# output_schematic_Z.net
KiCad netlist of a schematic drawn in EasyEDA
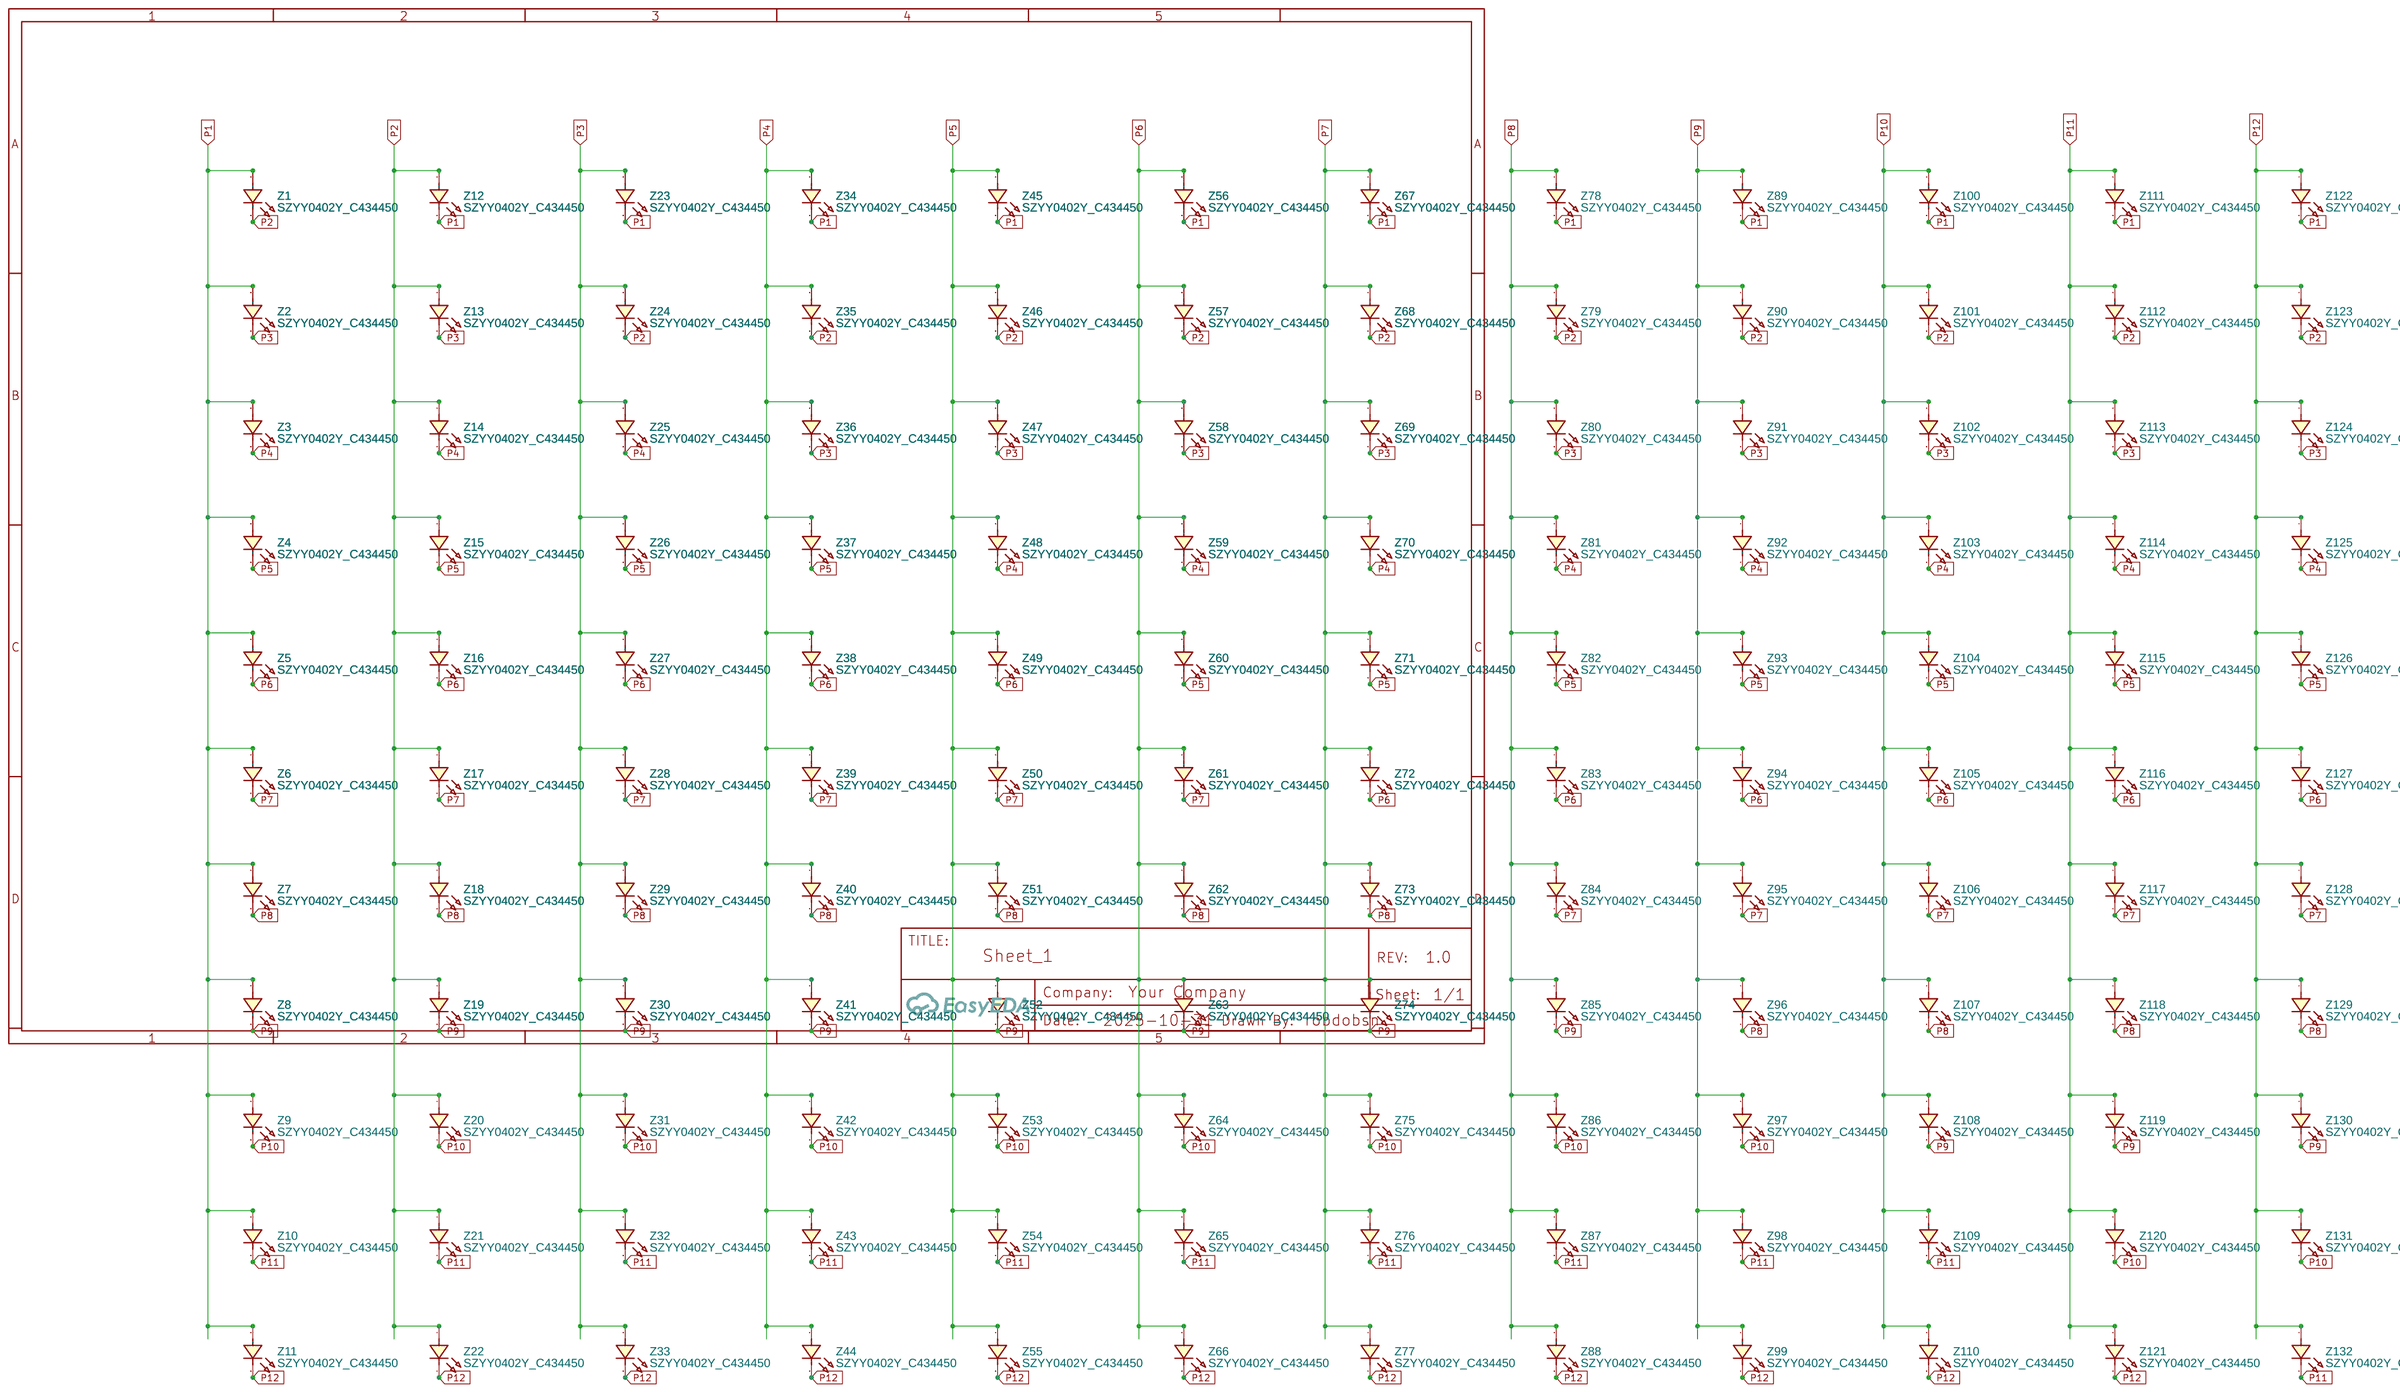
[diagram p0: schematic sheet]

(export (version "E")
  (design (tool "Eeschema 10.0.6"))
  (components
    (comp (ref "Z1")
      (value "SZYY0402Y_C434450")
      (fields (field (name "Manufacturer Part") "SZYY0402Y") (field (name "Manufacturer") "yongyu(永裕光电)"))
      (libsource (lib "") (part "SZYY0402Y_C434450"))
    )
    (comp (ref "Z2")
      (value "SZYY0402Y_C434450")
      (fields (field (name "Manufacturer Part") "SZYY0402Y") (field (name "Manufacturer") "yongyu(永裕光电)"))
      (libsource (lib "") (part "SZYY0402Y_C434450"))
    )
    (comp (ref "Z3")
      (value "SZYY0402Y_C434450")
      (fields (field (name "Manufacturer Part") "SZYY0402Y") (field (name "Manufacturer") "yongyu(永裕光电)"))
      (libsource (lib "") (part "SZYY0402Y_C434450"))
    )
    (comp (ref "Z4")
      (value "SZYY0402Y_C434450")
      (fields (field (name "Manufacturer Part") "SZYY0402Y") (field (name "Manufacturer") "yongyu(永裕光电)"))
      (libsource (lib "") (part "SZYY0402Y_C434450"))
    )
    (comp (ref "Z5")
      (value "SZYY0402Y_C434450")
      (fields (field (name "Manufacturer Part") "SZYY0402Y") (field (name "Manufacturer") "yongyu(永裕光电)"))
      (libsource (lib "") (part "SZYY0402Y_C434450"))
    )
    (comp (ref "Z6")
      (value "SZYY0402Y_C434450")
      (fields (field (name "Manufacturer Part") "SZYY0402Y") (field (name "Manufacturer") "yongyu(永裕光电)"))
      (libsource (lib "") (part "SZYY0402Y_C434450"))
    )
    (comp (ref "Z7")
      (value "SZYY0402Y_C434450")
      (fields (field (name "Manufacturer Part") "SZYY0402Y") (field (name "Manufacturer") "yongyu(永裕光电)"))
      (libsource (lib "") (part "SZYY0402Y_C434450"))
    )
    (comp (ref "Z8")
      (value "SZYY0402Y_C434450")
      (fields (field (name "Manufacturer Part") "SZYY0402Y") (field (name "Manufacturer") "yongyu(永裕光电)"))
      (libsource (lib "") (part "SZYY0402Y_C434450"))
    )
    (comp (ref "Z9")
      (value "SZYY0402Y_C434450")
      (fields (field (name "Manufacturer Part") "SZYY0402Y") (field (name "Manufacturer") "yongyu(永裕光电)"))
      (libsource (lib "") (part "SZYY0402Y_C434450"))
    )
    (comp (ref "Z10")
      (value "SZYY0402Y_C434450")
      (fields (field (name "Manufacturer Part") "SZYY0402Y") (field (name "Manufacturer") "yongyu(永裕光电)"))
      (libsource (lib "") (part "SZYY0402Y_C434450"))
    )
    (comp (ref "Z11")
      (value "SZYY0402Y_C434450")
      (fields (field (name "Manufacturer Part") "SZYY0402Y") (field (name "Manufacturer") "yongyu(永裕光电)"))
      (libsource (lib "") (part "SZYY0402Y_C434450"))
    )
    (comp (ref "Z12")
      (value "SZYY0402Y_C434450")
      (fields (field (name "Manufacturer Part") "SZYY0402Y") (field (name "Manufacturer") "yongyu(永裕光电)"))
      (libsource (lib "") (part "SZYY0402Y_C434450"))
    )
    (comp (ref "Z13")
      (value "SZYY0402Y_C434450")
      (fields (field (name "Manufacturer Part") "SZYY0402Y") (field (name "Manufacturer") "yongyu(永裕光电)"))
      (libsource (lib "") (part "SZYY0402Y_C434450"))
    )
    (comp (ref "Z14")
      (value "SZYY0402Y_C434450")
      (fields (field (name "Manufacturer Part") "SZYY0402Y") (field (name "Manufacturer") "yongyu(永裕光电)"))
      (libsource (lib "") (part "SZYY0402Y_C434450"))
    )
    (comp (ref "Z15")
      (value "SZYY0402Y_C434450")
      (fields (field (name "Manufacturer Part") "SZYY0402Y") (field (name "Manufacturer") "yongyu(永裕光电)"))
      (libsource (lib "") (part "SZYY0402Y_C434450"))
    )
    (comp (ref "Z16")
      (value "SZYY0402Y_C434450")
      (fields (field (name "Manufacturer Part") "SZYY0402Y") (field (name "Manufacturer") "yongyu(永裕光电)"))
      (libsource (lib "") (part "SZYY0402Y_C434450"))
    )
    (comp (ref "Z17")
      (value "SZYY0402Y_C434450")
      (fields (field (name "Manufacturer Part") "SZYY0402Y") (field (name "Manufacturer") "yongyu(永裕光电)"))
      (libsource (lib "") (part "SZYY0402Y_C434450"))
    )
    (comp (ref "Z18")
      (value "SZYY0402Y_C434450")
      (fields (field (name "Manufacturer Part") "SZYY0402Y") (field (name "Manufacturer") "yongyu(永裕光电)"))
      (libsource (lib "") (part "SZYY0402Y_C434450"))
    )
    (comp (ref "Z19")
      (value "SZYY0402Y_C434450")
      (fields (field (name "Manufacturer Part") "SZYY0402Y") (field (name "Manufacturer") "yongyu(永裕光电)"))
      (libsource (lib "") (part "SZYY0402Y_C434450"))
    )
    (comp (ref "Z20")
      (value "SZYY0402Y_C434450")
      (fields (field (name "Manufacturer Part") "SZYY0402Y") (field (name "Manufacturer") "yongyu(永裕光电)"))
      (libsource (lib "") (part "SZYY0402Y_C434450"))
    )
    (comp (ref "Z21")
      (value "SZYY0402Y_C434450")
      (fields (field (name "Manufacturer Part") "SZYY0402Y") (field (name "Manufacturer") "yongyu(永裕光电)"))
      (libsource (lib "") (part "SZYY0402Y_C434450"))
    )
    (comp (ref "Z22")
      (value "SZYY0402Y_C434450")
      (fields (field (name "Manufacturer Part") "SZYY0402Y") (field (name "Manufacturer") "yongyu(永裕光电)"))
      (libsource (lib "") (part "SZYY0402Y_C434450"))
    )
    (comp (ref "Z23")
      (value "SZYY0402Y_C434450")
      (fields (field (name "Manufacturer Part") "SZYY0402Y") (field (name "Manufacturer") "yongyu(永裕光电)"))
      (libsource (lib "") (part "SZYY0402Y_C434450"))
    )
    (comp (ref "Z24")
      (value "SZYY0402Y_C434450")
      (fields (field (name "Manufacturer Part") "SZYY0402Y") (field (name "Manufacturer") "yongyu(永裕光电)"))
      (libsource (lib "") (part "SZYY0402Y_C434450"))
    )
    (comp (ref "Z25")
      (value "SZYY0402Y_C434450")
      (fields (field (name "Manufacturer Part") "SZYY0402Y") (field (name "Manufacturer") "yongyu(永裕光电)"))
      (libsource (lib "") (part "SZYY0402Y_C434450"))
    )
    (comp (ref "Z26")
      (value "SZYY0402Y_C434450")
      (fields (field (name "Manufacturer Part") "SZYY0402Y") (field (name "Manufacturer") "yongyu(永裕光电)"))
      (libsource (lib "") (part "SZYY0402Y_C434450"))
    )
    (comp (ref "Z27")
      (value "SZYY0402Y_C434450")
      (fields (field (name "Manufacturer Part") "SZYY0402Y") (field (name "Manufacturer") "yongyu(永裕光电)"))
      (libsource (lib "") (part "SZYY0402Y_C434450"))
    )
    (comp (ref "Z28")
      (value "SZYY0402Y_C434450")
      (fields (field (name "Manufacturer Part") "SZYY0402Y") (field (name "Manufacturer") "yongyu(永裕光电)"))
      (libsource (lib "") (part "SZYY0402Y_C434450"))
    )
    (comp (ref "Z29")
      (value "SZYY0402Y_C434450")
      (fields (field (name "Manufacturer Part") "SZYY0402Y") (field (name "Manufacturer") "yongyu(永裕光电)"))
      (libsource (lib "") (part "SZYY0402Y_C434450"))
    )
    (comp (ref "Z30")
      (value "SZYY0402Y_C434450")
      (fields (field (name "Manufacturer Part") "SZYY0402Y") (field (name "Manufacturer") "yongyu(永裕光电)"))
      (libsource (lib "") (part "SZYY0402Y_C434450"))
    )
    (comp (ref "Z31")
      (value "SZYY0402Y_C434450")
      (fields (field (name "Manufacturer Part") "SZYY0402Y") (field (name "Manufacturer") "yongyu(永裕光电)"))
      (libsource (lib "") (part "SZYY0402Y_C434450"))
    )
    (comp (ref "Z32")
      (value "SZYY0402Y_C434450")
      (fields (field (name "Manufacturer Part") "SZYY0402Y") (field (name "Manufacturer") "yongyu(永裕光电)"))
      (libsource (lib "") (part "SZYY0402Y_C434450"))
    )
    (comp (ref "Z33")
      (value "SZYY0402Y_C434450")
      (fields (field (name "Manufacturer Part") "SZYY0402Y") (field (name "Manufacturer") "yongyu(永裕光电)"))
      (libsource (lib "") (part "SZYY0402Y_C434450"))
    )
    (comp (ref "Z34")
      (value "SZYY0402Y_C434450")
      (fields (field (name "Manufacturer Part") "SZYY0402Y") (field (name "Manufacturer") "yongyu(永裕光电)"))
      (libsource (lib "") (part "SZYY0402Y_C434450"))
    )
    (comp (ref "Z35")
      (value "SZYY0402Y_C434450")
      (fields (field (name "Manufacturer Part") "SZYY0402Y") (field (name "Manufacturer") "yongyu(永裕光电)"))
      (libsource (lib "") (part "SZYY0402Y_C434450"))
    )
    (comp (ref "Z36")
      (value "SZYY0402Y_C434450")
      (fields (field (name "Manufacturer Part") "SZYY0402Y") (field (name "Manufacturer") "yongyu(永裕光电)"))
      (libsource (lib "") (part "SZYY0402Y_C434450"))
    )
    (comp (ref "Z37")
      (value "SZYY0402Y_C434450")
      (fields (field (name "Manufacturer Part") "SZYY0402Y") (field (name "Manufacturer") "yongyu(永裕光电)"))
      (libsource (lib "") (part "SZYY0402Y_C434450"))
    )
    (comp (ref "Z38")
      (value "SZYY0402Y_C434450")
      (fields (field (name "Manufacturer Part") "SZYY0402Y") (field (name "Manufacturer") "yongyu(永裕光电)"))
      (libsource (lib "") (part "SZYY0402Y_C434450"))
    )
    (comp (ref "Z39")
      (value "SZYY0402Y_C434450")
      (fields (field (name "Manufacturer Part") "SZYY0402Y") (field (name "Manufacturer") "yongyu(永裕光电)"))
      (libsource (lib "") (part "SZYY0402Y_C434450"))
    )
    (comp (ref "Z40")
      (value "SZYY0402Y_C434450")
      (fields (field (name "Manufacturer Part") "SZYY0402Y") (field (name "Manufacturer") "yongyu(永裕光电)"))
      (libsource (lib "") (part "SZYY0402Y_C434450"))
    )
    (comp (ref "Z41")
      (value "SZYY0402Y_C434450")
      (fields (field (name "Manufacturer Part") "SZYY0402Y") (field (name "Manufacturer") "yongyu(永裕光电)"))
      (libsource (lib "") (part "SZYY0402Y_C434450"))
    )
    (comp (ref "Z42")
      (value "SZYY0402Y_C434450")
      (fields (field (name "Manufacturer Part") "SZYY0402Y") (field (name "Manufacturer") "yongyu(永裕光电)"))
      (libsource (lib "") (part "SZYY0402Y_C434450"))
    )
    (comp (ref "Z43")
      (value "SZYY0402Y_C434450")
      (fields (field (name "Manufacturer Part") "SZYY0402Y") (field (name "Manufacturer") "yongyu(永裕光电)"))
      (libsource (lib "") (part "SZYY0402Y_C434450"))
    )
    (comp (ref "Z44")
      (value "SZYY0402Y_C434450")
      (fields (field (name "Manufacturer Part") "SZYY0402Y") (field (name "Manufacturer") "yongyu(永裕光电)"))
      (libsource (lib "") (part "SZYY0402Y_C434450"))
    )
    (comp (ref "Z45")
      (value "SZYY0402Y_C434450")
      (fields (field (name "Manufacturer Part") "SZYY0402Y") (field (name "Manufacturer") "yongyu(永裕光电)"))
      (libsource (lib "") (part "SZYY0402Y_C434450"))
    )
    (comp (ref "Z46")
      (value "SZYY0402Y_C434450")
      (fields (field (name "Manufacturer Part") "SZYY0402Y") (field (name "Manufacturer") "yongyu(永裕光电)"))
      (libsource (lib "") (part "SZYY0402Y_C434450"))
    )
    (comp (ref "Z47")
      (value "SZYY0402Y_C434450")
      (fields (field (name "Manufacturer Part") "SZYY0402Y") (field (name "Manufacturer") "yongyu(永裕光电)"))
      (libsource (lib "") (part "SZYY0402Y_C434450"))
    )
    (comp (ref "Z48")
      (value "SZYY0402Y_C434450")
      (fields (field (name "Manufacturer Part") "SZYY0402Y") (field (name "Manufacturer") "yongyu(永裕光电)"))
      (libsource (lib "") (part "SZYY0402Y_C434450"))
    )
    (comp (ref "Z49")
      (value "SZYY0402Y_C434450")
      (fields (field (name "Manufacturer Part") "SZYY0402Y") (field (name "Manufacturer") "yongyu(永裕光电)"))
      (libsource (lib "") (part "SZYY0402Y_C434450"))
    )
    (comp (ref "Z50")
      (value "SZYY0402Y_C434450")
      (fields (field (name "Manufacturer Part") "SZYY0402Y") (field (name "Manufacturer") "yongyu(永裕光电)"))
      (libsource (lib "") (part "SZYY0402Y_C434450"))
    )
    (comp (ref "Z51")
      (value "SZYY0402Y_C434450")
      (fields (field (name "Manufacturer Part") "SZYY0402Y") (field (name "Manufacturer") "yongyu(永裕光电)"))
      (libsource (lib "") (part "SZYY0402Y_C434450"))
    )
    (comp (ref "Z52")
      (value "SZYY0402Y_C434450")
      (fields (field (name "Manufacturer Part") "SZYY0402Y") (field (name "Manufacturer") "yongyu(永裕光电)"))
      (libsource (lib "") (part "SZYY0402Y_C434450"))
    )
    (comp (ref "Z53")
      (value "SZYY0402Y_C434450")
      (fields (field (name "Manufacturer Part") "SZYY0402Y") (field (name "Manufacturer") "yongyu(永裕光电)"))
      (libsource (lib "") (part "SZYY0402Y_C434450"))
    )
    (comp (ref "Z54")
      (value "SZYY0402Y_C434450")
      (fields (field (name "Manufacturer Part") "SZYY0402Y") (field (name "Manufacturer") "yongyu(永裕光电)"))
      (libsource (lib "") (part "SZYY0402Y_C434450"))
    )
    (comp (ref "Z55")
      (value "SZYY0402Y_C434450")
      (fields (field (name "Manufacturer Part") "SZYY0402Y") (field (name "Manufacturer") "yongyu(永裕光电)"))
      (libsource (lib "") (part "SZYY0402Y_C434450"))
    )
    (comp (ref "Z56")
      (value "SZYY0402Y_C434450")
      (fields (field (name "Manufacturer Part") "SZYY0402Y") (field (name "Manufacturer") "yongyu(永裕光电)"))
      (libsource (lib "") (part "SZYY0402Y_C434450"))
    )
    (comp (ref "Z57")
      (value "SZYY0402Y_C434450")
      (fields (field (name "Manufacturer Part") "SZYY0402Y") (field (name "Manufacturer") "yongyu(永裕光电)"))
      (libsource (lib "") (part "SZYY0402Y_C434450"))
    )
    (comp (ref "Z58")
      (value "SZYY0402Y_C434450")
      (fields (field (name "Manufacturer Part") "SZYY0402Y") (field (name "Manufacturer") "yongyu(永裕光电)"))
      (libsource (lib "") (part "SZYY0402Y_C434450"))
    )
    (comp (ref "Z59")
      (value "SZYY0402Y_C434450")
      (fields (field (name "Manufacturer Part") "SZYY0402Y") (field (name "Manufacturer") "yongyu(永裕光电)"))
      (libsource (lib "") (part "SZYY0402Y_C434450"))
    )
    (comp (ref "Z60")
      (value "SZYY0402Y_C434450")
      (fields (field (name "Manufacturer Part") "SZYY0402Y") (field (name "Manufacturer") "yongyu(永裕光电)"))
      (libsource (lib "") (part "SZYY0402Y_C434450"))
    )
    (comp (ref "Z61")
      (value "SZYY0402Y_C434450")
      (fields (field (name "Manufacturer Part") "SZYY0402Y") (field (name "Manufacturer") "yongyu(永裕光电)"))
      (libsource (lib "") (part "SZYY0402Y_C434450"))
    )
    (comp (ref "Z62")
      (value "SZYY0402Y_C434450")
      (fields (field (name "Manufacturer Part") "SZYY0402Y") (field (name "Manufacturer") "yongyu(永裕光电)"))
      (libsource (lib "") (part "SZYY0402Y_C434450"))
    )
    (comp (ref "Z63")
      (value "SZYY0402Y_C434450")
      (fields (field (name "Manufacturer Part") "SZYY0402Y") (field (name "Manufacturer") "yongyu(永裕光电)"))
      (libsource (lib "") (part "SZYY0402Y_C434450"))
    )
    (comp (ref "Z64")
      (value "SZYY0402Y_C434450")
      (fields (field (name "Manufacturer Part") "SZYY0402Y") (field (name "Manufacturer") "yongyu(永裕光电)"))
      (libsource (lib "") (part "SZYY0402Y_C434450"))
    )
    (comp (ref "Z65")
      (value "SZYY0402Y_C434450")
      (fields (field (name "Manufacturer Part") "SZYY0402Y") (field (name "Manufacturer") "yongyu(永裕光电)"))
      (libsource (lib "") (part "SZYY0402Y_C434450"))
    )
    (comp (ref "Z66")
      (value "SZYY0402Y_C434450")
      (fields (field (name "Manufacturer Part") "SZYY0402Y") (field (name "Manufacturer") "yongyu(永裕光电)"))
      (libsource (lib "") (part "SZYY0402Y_C434450"))
    )
    (comp (ref "Z67")
      (value "SZYY0402Y_C434450")
      (fields (field (name "Manufacturer Part") "SZYY0402Y") (field (name "Manufacturer") "yongyu(永裕光电)"))
      (libsource (lib "") (part "SZYY0402Y_C434450"))
    )
    (comp (ref "Z68")
      (value "SZYY0402Y_C434450")
      (fields (field (name "Manufacturer Part") "SZYY0402Y") (field (name "Manufacturer") "yongyu(永裕光电)"))
      (libsource (lib "") (part "SZYY0402Y_C434450"))
    )
    (comp (ref "Z69")
      (value "SZYY0402Y_C434450")
      (fields (field (name "Manufacturer Part") "SZYY0402Y") (field (name "Manufacturer") "yongyu(永裕光电)"))
      (libsource (lib "") (part "SZYY0402Y_C434450"))
    )
    (comp (ref "Z70")
      (value "SZYY0402Y_C434450")
      (fields (field (name "Manufacturer Part") "SZYY0402Y") (field (name "Manufacturer") "yongyu(永裕光电)"))
      (libsource (lib "") (part "SZYY0402Y_C434450"))
    )
    (comp (ref "Z71")
      (value "SZYY0402Y_C434450")
      (fields (field (name "Manufacturer Part") "SZYY0402Y") (field (name "Manufacturer") "yongyu(永裕光电)"))
      (libsource (lib "") (part "SZYY0402Y_C434450"))
    )
    (comp (ref "Z72")
      (value "SZYY0402Y_C434450")
      (fields (field (name "Manufacturer Part") "SZYY0402Y") (field (name "Manufacturer") "yongyu(永裕光电)"))
      (libsource (lib "") (part "SZYY0402Y_C434450"))
    )
    (comp (ref "Z73")
      (value "SZYY0402Y_C434450")
      (fields (field (name "Manufacturer Part") "SZYY0402Y") (field (name "Manufacturer") "yongyu(永裕光电)"))
      (libsource (lib "") (part "SZYY0402Y_C434450"))
    )
    (comp (ref "Z74")
      (value "SZYY0402Y_C434450")
      (fields (field (name "Manufacturer Part") "SZYY0402Y") (field (name "Manufacturer") "yongyu(永裕光电)"))
      (libsource (lib "") (part "SZYY0402Y_C434450"))
    )
    (comp (ref "Z75")
      (value "SZYY0402Y_C434450")
      (fields (field (name "Manufacturer Part") "SZYY0402Y") (field (name "Manufacturer") "yongyu(永裕光电)"))
      (libsource (lib "") (part "SZYY0402Y_C434450"))
    )
    (comp (ref "Z76")
      (value "SZYY0402Y_C434450")
      (fields (field (name "Manufacturer Part") "SZYY0402Y") (field (name "Manufacturer") "yongyu(永裕光电)"))
      (libsource (lib "") (part "SZYY0402Y_C434450"))
    )
    (comp (ref "Z77")
      (value "SZYY0402Y_C434450")
      (fields (field (name "Manufacturer Part") "SZYY0402Y") (field (name "Manufacturer") "yongyu(永裕光电)"))
      (libsource (lib "") (part "SZYY0402Y_C434450"))
    )
    (comp (ref "Z78")
      (value "SZYY0402Y_C434450")
      (fields (field (name "Manufacturer Part") "SZYY0402Y") (field (name "Manufacturer") "yongyu(永裕光电)"))
      (libsource (lib "") (part "SZYY0402Y_C434450"))
    )
    (comp (ref "Z79")
      (value "SZYY0402Y_C434450")
      (fields (field (name "Manufacturer Part") "SZYY0402Y") (field (name "Manufacturer") "yongyu(永裕光电)"))
      (libsource (lib "") (part "SZYY0402Y_C434450"))
    )
    (comp (ref "Z80")
      (value "SZYY0402Y_C434450")
      (fields (field (name "Manufacturer Part") "SZYY0402Y") (field (name "Manufacturer") "yongyu(永裕光电)"))
      (libsource (lib "") (part "SZYY0402Y_C434450"))
    )
    (comp (ref "Z81")
      (value "SZYY0402Y_C434450")
      (fields (field (name "Manufacturer Part") "SZYY0402Y") (field (name "Manufacturer") "yongyu(永裕光电)"))
      (libsource (lib "") (part "SZYY0402Y_C434450"))
    )
    (comp (ref "Z82")
      (value "SZYY0402Y_C434450")
      (fields (field (name "Manufacturer Part") "SZYY0402Y") (field (name "Manufacturer") "yongyu(永裕光电)"))
      (libsource (lib "") (part "SZYY0402Y_C434450"))
    )
    (comp (ref "Z83")
      (value "SZYY0402Y_C434450")
      (fields (field (name "Manufacturer Part") "SZYY0402Y") (field (name "Manufacturer") "yongyu(永裕光电)"))
      (libsource (lib "") (part "SZYY0402Y_C434450"))
    )
    (comp (ref "Z84")
      (value "SZYY0402Y_C434450")
      (fields (field (name "Manufacturer Part") "SZYY0402Y") (field (name "Manufacturer") "yongyu(永裕光电)"))
      (libsource (lib "") (part "SZYY0402Y_C434450"))
    )
    (comp (ref "Z85")
      (value "SZYY0402Y_C434450")
      (fields (field (name "Manufacturer Part") "SZYY0402Y") (field (name "Manufacturer") "yongyu(永裕光电)"))
      (libsource (lib "") (part "SZYY0402Y_C434450"))
    )
    (comp (ref "Z86")
      (value "SZYY0402Y_C434450")
      (fields (field (name "Manufacturer Part") "SZYY0402Y") (field (name "Manufacturer") "yongyu(永裕光电)"))
      (libsource (lib "") (part "SZYY0402Y_C434450"))
    )
    (comp (ref "Z87")
      (value "SZYY0402Y_C434450")
      (fields (field (name "Manufacturer Part") "SZYY0402Y") (field (name "Manufacturer") "yongyu(永裕光电)"))
      (libsource (lib "") (part "SZYY0402Y_C434450"))
    )
    (comp (ref "Z88")
      (value "SZYY0402Y_C434450")
      (fields (field (name "Manufacturer Part") "SZYY0402Y") (field (name "Manufacturer") "yongyu(永裕光电)"))
      (libsource (lib "") (part "SZYY0402Y_C434450"))
    )
    (comp (ref "Z89")
      (value "SZYY0402Y_C434450")
      (fields (field (name "Manufacturer Part") "SZYY0402Y") (field (name "Manufacturer") "yongyu(永裕光电)"))
      (libsource (lib "") (part "SZYY0402Y_C434450"))
    )
    (comp (ref "Z90")
      (value "SZYY0402Y_C434450")
      (fields (field (name "Manufacturer Part") "SZYY0402Y") (field (name "Manufacturer") "yongyu(永裕光电)"))
      (libsource (lib "") (part "SZYY0402Y_C434450"))
    )
    (comp (ref "Z91")
      (value "SZYY0402Y_C434450")
      (fields (field (name "Manufacturer Part") "SZYY0402Y") (field (name "Manufacturer") "yongyu(永裕光电)"))
      (libsource (lib "") (part "SZYY0402Y_C434450"))
    )
    (comp (ref "Z92")
      (value "SZYY0402Y_C434450")
      (fields (field (name "Manufacturer Part") "SZYY0402Y") (field (name "Manufacturer") "yongyu(永裕光电)"))
      (libsource (lib "") (part "SZYY0402Y_C434450"))
    )
    (comp (ref "Z93")
      (value "SZYY0402Y_C434450")
      (fields (field (name "Manufacturer Part") "SZYY0402Y") (field (name "Manufacturer") "yongyu(永裕光电)"))
      (libsource (lib "") (part "SZYY0402Y_C434450"))
    )
    (comp (ref "Z94")
      (value "SZYY0402Y_C434450")
      (fields (field (name "Manufacturer Part") "SZYY0402Y") (field (name "Manufacturer") "yongyu(永裕光电)"))
      (libsource (lib "") (part "SZYY0402Y_C434450"))
    )
    (comp (ref "Z95")
      (value "SZYY0402Y_C434450")
      (fields (field (name "Manufacturer Part") "SZYY0402Y") (field (name "Manufacturer") "yongyu(永裕光电)"))
      (libsource (lib "") (part "SZYY0402Y_C434450"))
    )
    (comp (ref "Z96")
      (value "SZYY0402Y_C434450")
      (fields (field (name "Manufacturer Part") "SZYY0402Y") (field (name "Manufacturer") "yongyu(永裕光电)"))
      (libsource (lib "") (part "SZYY0402Y_C434450"))
    )
    (comp (ref "Z97")
      (value "SZYY0402Y_C434450")
      (fields (field (name "Manufacturer Part") "SZYY0402Y") (field (name "Manufacturer") "yongyu(永裕光电)"))
      (libsource (lib "") (part "SZYY0402Y_C434450"))
    )
    (comp (ref "Z98")
      (value "SZYY0402Y_C434450")
      (fields (field (name "Manufacturer Part") "SZYY0402Y") (field (name "Manufacturer") "yongyu(永裕光电)"))
      (libsource (lib "") (part "SZYY0402Y_C434450"))
    )
    (comp (ref "Z99")
      (value "SZYY0402Y_C434450")
      (fields (field (name "Manufacturer Part") "SZYY0402Y") (field (name "Manufacturer") "yongyu(永裕光电)"))
      (libsource (lib "") (part "SZYY0402Y_C434450"))
    )
    (comp (ref "Z100")
      (value "SZYY0402Y_C434450")
      (fields (field (name "Manufacturer Part") "SZYY0402Y") (field (name "Manufacturer") "yongyu(永裕光电)"))
      (libsource (lib "") (part "SZYY0402Y_C434450"))
    )
    (comp (ref "Z101")
      (value "SZYY0402Y_C434450")
      (fields (field (name "Manufacturer Part") "SZYY0402Y") (field (name "Manufacturer") "yongyu(永裕光电)"))
      (libsource (lib "") (part "SZYY0402Y_C434450"))
    )
    (comp (ref "Z102")
      (value "SZYY0402Y_C434450")
      (fields (field (name "Manufacturer Part") "SZYY0402Y") (field (name "Manufacturer") "yongyu(永裕光电)"))
      (libsource (lib "") (part "SZYY0402Y_C434450"))
    )
    (comp (ref "Z103")
      (value "SZYY0402Y_C434450")
      (fields (field (name "Manufacturer Part") "SZYY0402Y") (field (name "Manufacturer") "yongyu(永裕光电)"))
      (libsource (lib "") (part "SZYY0402Y_C434450"))
    )
    (comp (ref "Z104")
      (value "SZYY0402Y_C434450")
      (fields (field (name "Manufacturer Part") "SZYY0402Y") (field (name "Manufacturer") "yongyu(永裕光电)"))
      (libsource (lib "") (part "SZYY0402Y_C434450"))
    )
    (comp (ref "Z105")
      (value "SZYY0402Y_C434450")
      (fields (field (name "Manufacturer Part") "SZYY0402Y") (field (name "Manufacturer") "yongyu(永裕光电)"))
      (libsource (lib "") (part "SZYY0402Y_C434450"))
    )
    (comp (ref "Z106")
      (value "SZYY0402Y_C434450")
      (fields (field (name "Manufacturer Part") "SZYY0402Y") (field (name "Manufacturer") "yongyu(永裕光电)"))
      (libsource (lib "") (part "SZYY0402Y_C434450"))
    )
    (comp (ref "Z107")
      (value "SZYY0402Y_C434450")
      (fields (field (name "Manufacturer Part") "SZYY0402Y") (field (name "Manufacturer") "yongyu(永裕光电)"))
      (libsource (lib "") (part "SZYY0402Y_C434450"))
    )
    (comp (ref "Z108")
      (value "SZYY0402Y_C434450")
      (fields (field (name "Manufacturer Part") "SZYY0402Y") (field (name "Manufacturer") "yongyu(永裕光电)"))
      (libsource (lib "") (part "SZYY0402Y_C434450"))
    )
    (comp (ref "Z109")
      (value "SZYY0402Y_C434450")
      (fields (field (name "Manufacturer Part") "SZYY0402Y") (field (name "Manufacturer") "yongyu(永裕光电)"))
      (libsource (lib "") (part "SZYY0402Y_C434450"))
    )
    (comp (ref "Z110")
      (value "SZYY0402Y_C434450")
      (fields (field (name "Manufacturer Part") "SZYY0402Y") (field (name "Manufacturer") "yongyu(永裕光电)"))
      (libsource (lib "") (part "SZYY0402Y_C434450"))
    )
    (comp (ref "Z111")
      (value "SZYY0402Y_C434450")
      (fields (field (name "Manufacturer Part") "SZYY0402Y") (field (name "Manufacturer") "yongyu(永裕光电)"))
      (libsource (lib "") (part "SZYY0402Y_C434450"))
    )
    (comp (ref "Z112")
      (value "SZYY0402Y_C434450")
      (fields (field (name "Manufacturer Part") "SZYY0402Y") (field (name "Manufacturer") "yongyu(永裕光电)"))
      (libsource (lib "") (part "SZYY0402Y_C434450"))
    )
    (comp (ref "Z113")
      (value "SZYY0402Y_C434450")
      (fields (field (name "Manufacturer Part") "SZYY0402Y") (field (name "Manufacturer") "yongyu(永裕光电)"))
      (libsource (lib "") (part "SZYY0402Y_C434450"))
    )
    (comp (ref "Z114")
      (value "SZYY0402Y_C434450")
      (fields (field (name "Manufacturer Part") "SZYY0402Y") (field (name "Manufacturer") "yongyu(永裕光电)"))
      (libsource (lib "") (part "SZYY0402Y_C434450"))
    )
    (comp (ref "Z115")
      (value "SZYY0402Y_C434450")
      (fields (field (name "Manufacturer Part") "SZYY0402Y") (field (name "Manufacturer") "yongyu(永裕光电)"))
      (libsource (lib "") (part "SZYY0402Y_C434450"))
    )
    (comp (ref "Z116")
      (value "SZYY0402Y_C434450")
      (fields (field (name "Manufacturer Part") "SZYY0402Y") (field (name "Manufacturer") "yongyu(永裕光电)"))
      (libsource (lib "") (part "SZYY0402Y_C434450"))
    )
    (comp (ref "Z117")
      (value "SZYY0402Y_C434450")
      (fields (field (name "Manufacturer Part") "SZYY0402Y") (field (name "Manufacturer") "yongyu(永裕光电)"))
      (libsource (lib "") (part "SZYY0402Y_C434450"))
    )
    (comp (ref "Z118")
      (value "SZYY0402Y_C434450")
      (fields (field (name "Manufacturer Part") "SZYY0402Y") (field (name "Manufacturer") "yongyu(永裕光电)"))
      (libsource (lib "") (part "SZYY0402Y_C434450"))
    )
    (comp (ref "Z119")
      (value "SZYY0402Y_C434450")
      (fields (field (name "Manufacturer Part") "SZYY0402Y") (field (name "Manufacturer") "yongyu(永裕光电)"))
      (libsource (lib "") (part "SZYY0402Y_C434450"))
    )
    (comp (ref "Z120")
      (value "SZYY0402Y_C434450")
      (fields (field (name "Manufacturer Part") "SZYY0402Y") (field (name "Manufacturer") "yongyu(永裕光电)"))
      (libsource (lib "") (part "SZYY0402Y_C434450"))
    )
    (comp (ref "Z121")
      (value "SZYY0402Y_C434450")
      (fields (field (name "Manufacturer Part") "SZYY0402Y") (field (name "Manufacturer") "yongyu(永裕光电)"))
      (libsource (lib "") (part "SZYY0402Y_C434450"))
    )
    (comp (ref "Z122")
      (value "SZYY0402Y_C434450")
      (fields (field (name "Manufacturer Part") "SZYY0402Y") (field (name "Manufacturer") "yongyu(永裕光电)"))
      (libsource (lib "") (part "SZYY0402Y_C434450"))
    )
    (comp (ref "Z123")
      (value "SZYY0402Y_C434450")
      (fields (field (name "Manufacturer Part") "SZYY0402Y") (field (name "Manufacturer") "yongyu(永裕光电)"))
      (libsource (lib "") (part "SZYY0402Y_C434450"))
    )
    (comp (ref "Z124")
      (value "SZYY0402Y_C434450")
      (fields (field (name "Manufacturer Part") "SZYY0402Y") (field (name "Manufacturer") "yongyu(永裕光电)"))
      (libsource (lib "") (part "SZYY0402Y_C434450"))
    )
    (comp (ref "Z125")
      (value "SZYY0402Y_C434450")
      (fields (field (name "Manufacturer Part") "SZYY0402Y") (field (name "Manufacturer") "yongyu(永裕光电)"))
      (libsource (lib "") (part "SZYY0402Y_C434450"))
    )
    (comp (ref "Z126")
      (value "SZYY0402Y_C434450")
      (fields (field (name "Manufacturer Part") "SZYY0402Y") (field (name "Manufacturer") "yongyu(永裕光电)"))
      (libsource (lib "") (part "SZYY0402Y_C434450"))
    )
    (comp (ref "Z127")
      (value "SZYY0402Y_C434450")
      (fields (field (name "Manufacturer Part") "SZYY0402Y") (field (name "Manufacturer") "yongyu(永裕光电)"))
      (libsource (lib "") (part "SZYY0402Y_C434450"))
    )
    (comp (ref "Z128")
      (value "SZYY0402Y_C434450")
      (fields (field (name "Manufacturer Part") "SZYY0402Y") (field (name "Manufacturer") "yongyu(永裕光电)"))
      (libsource (lib "") (part "SZYY0402Y_C434450"))
    )
    (comp (ref "Z129")
      (value "SZYY0402Y_C434450")
      (fields (field (name "Manufacturer Part") "SZYY0402Y") (field (name "Manufacturer") "yongyu(永裕光电)"))
      (libsource (lib "") (part "SZYY0402Y_C434450"))
    )
    (comp (ref "Z130")
      (value "SZYY0402Y_C434450")
      (fields (field (name "Manufacturer Part") "SZYY0402Y") (field (name "Manufacturer") "yongyu(永裕光电)"))
      (libsource (lib "") (part "SZYY0402Y_C434450"))
    )
    (comp (ref "Z131")
      (value "SZYY0402Y_C434450")
      (fields (field (name "Manufacturer Part") "SZYY0402Y") (field (name "Manufacturer") "yongyu(永裕光电)"))
      (libsource (lib "") (part "SZYY0402Y_C434450"))
    )
    (comp (ref "Z132")
      (value "SZYY0402Y_C434450")
      (fields (field (name "Manufacturer Part") "SZYY0402Y") (field (name "Manufacturer") "yongyu(永裕光电)"))
      (libsource (lib "") (part "SZYY0402Y_C434450"))
    )
  )
  (nets
    (net (code "1") (name "P1") (class "Default")
      (node (ref "Z1") (pin "1") (pinfunction "A_1") (pintype "unspecified"))
      (node (ref "Z10") (pin "1") (pinfunction "A_1") (pintype "unspecified"))
      (node (ref "Z100") (pin "2") (pinfunction "K_2") (pintype "unspecified"))
      (node (ref "Z11") (pin "1") (pinfunction "A_1") (pintype "unspecified"))
      (node (ref "Z111") (pin "2") (pinfunction "K_2") (pintype "unspecified"))
      (node (ref "Z12") (pin "2") (pinfunction "K_2") (pintype "unspecified"))
      (node (ref "Z122") (pin "2") (pinfunction "K_2") (pintype "unspecified"))
      (node (ref "Z2") (pin "1") (pinfunction "A_1") (pintype "unspecified"))
      (node (ref "Z23") (pin "2") (pinfunction "K_2") (pintype "unspecified"))
      (node (ref "Z3") (pin "1") (pinfunction "A_1") (pintype "unspecified"))
      (node (ref "Z34") (pin "2") (pinfunction "K_2") (pintype "unspecified"))
      (node (ref "Z4") (pin "1") (pinfunction "A_1") (pintype "unspecified"))
      (node (ref "Z45") (pin "2") (pinfunction "K_2") (pintype "unspecified"))
      (node (ref "Z5") (pin "1") (pinfunction "A_1") (pintype "unspecified"))
      (node (ref "Z56") (pin "2") (pinfunction "K_2") (pintype "unspecified"))
      (node (ref "Z6") (pin "1") (pinfunction "A_1") (pintype "unspecified"))
      (node (ref "Z67") (pin "2") (pinfunction "K_2") (pintype "unspecified"))
      (node (ref "Z7") (pin "1") (pinfunction "A_1") (pintype "unspecified"))
      (node (ref "Z78") (pin "2") (pinfunction "K_2") (pintype "unspecified"))
      (node (ref "Z8") (pin "1") (pinfunction "A_1") (pintype "unspecified"))
      (node (ref "Z89") (pin "2") (pinfunction "K_2") (pintype "unspecified"))
      (node (ref "Z9") (pin "1") (pinfunction "A_1") (pintype "unspecified"))
    )
    (net (code "2") (name "P2") (class "Default")
      (node (ref "Z1") (pin "2") (pinfunction "K_2") (pintype "unspecified"))
      (node (ref "Z101") (pin "2") (pinfunction "K_2") (pintype "unspecified"))
      (node (ref "Z112") (pin "2") (pinfunction "K_2") (pintype "unspecified"))
      (node (ref "Z12") (pin "1") (pinfunction "A_1") (pintype "unspecified"))
      (node (ref "Z123") (pin "2") (pinfunction "K_2") (pintype "unspecified"))
      (node (ref "Z13") (pin "1") (pinfunction "A_1") (pintype "unspecified"))
      (node (ref "Z14") (pin "1") (pinfunction "A_1") (pintype "unspecified"))
      (node (ref "Z15") (pin "1") (pinfunction "A_1") (pintype "unspecified"))
      (node (ref "Z16") (pin "1") (pinfunction "A_1") (pintype "unspecified"))
      (node (ref "Z17") (pin "1") (pinfunction "A_1") (pintype "unspecified"))
      (node (ref "Z18") (pin "1") (pinfunction "A_1") (pintype "unspecified"))
      (node (ref "Z19") (pin "1") (pinfunction "A_1") (pintype "unspecified"))
      (node (ref "Z20") (pin "1") (pinfunction "A_1") (pintype "unspecified"))
      (node (ref "Z21") (pin "1") (pinfunction "A_1") (pintype "unspecified"))
      (node (ref "Z22") (pin "1") (pinfunction "A_1") (pintype "unspecified"))
      (node (ref "Z24") (pin "2") (pinfunction "K_2") (pintype "unspecified"))
      (node (ref "Z35") (pin "2") (pinfunction "K_2") (pintype "unspecified"))
      (node (ref "Z46") (pin "2") (pinfunction "K_2") (pintype "unspecified"))
      (node (ref "Z57") (pin "2") (pinfunction "K_2") (pintype "unspecified"))
      (node (ref "Z68") (pin "2") (pinfunction "K_2") (pintype "unspecified"))
      (node (ref "Z79") (pin "2") (pinfunction "K_2") (pintype "unspecified"))
      (node (ref "Z90") (pin "2") (pinfunction "K_2") (pintype "unspecified"))
    )
    (net (code "3") (name "P3") (class "Default")
      (node (ref "Z102") (pin "2") (pinfunction "K_2") (pintype "unspecified"))
      (node (ref "Z113") (pin "2") (pinfunction "K_2") (pintype "unspecified"))
      (node (ref "Z124") (pin "2") (pinfunction "K_2") (pintype "unspecified"))
      (node (ref "Z13") (pin "2") (pinfunction "K_2") (pintype "unspecified"))
      (node (ref "Z2") (pin "2") (pinfunction "K_2") (pintype "unspecified"))
      (node (ref "Z23") (pin "1") (pinfunction "A_1") (pintype "unspecified"))
      (node (ref "Z24") (pin "1") (pinfunction "A_1") (pintype "unspecified"))
      (node (ref "Z25") (pin "1") (pinfunction "A_1") (pintype "unspecified"))
      (node (ref "Z26") (pin "1") (pinfunction "A_1") (pintype "unspecified"))
      (node (ref "Z27") (pin "1") (pinfunction "A_1") (pintype "unspecified"))
      (node (ref "Z28") (pin "1") (pinfunction "A_1") (pintype "unspecified"))
      (node (ref "Z29") (pin "1") (pinfunction "A_1") (pintype "unspecified"))
      (node (ref "Z30") (pin "1") (pinfunction "A_1") (pintype "unspecified"))
      (node (ref "Z31") (pin "1") (pinfunction "A_1") (pintype "unspecified"))
      (node (ref "Z32") (pin "1") (pinfunction "A_1") (pintype "unspecified"))
      (node (ref "Z33") (pin "1") (pinfunction "A_1") (pintype "unspecified"))
      (node (ref "Z36") (pin "2") (pinfunction "K_2") (pintype "unspecified"))
      (node (ref "Z47") (pin "2") (pinfunction "K_2") (pintype "unspecified"))
      (node (ref "Z58") (pin "2") (pinfunction "K_2") (pintype "unspecified"))
      (node (ref "Z69") (pin "2") (pinfunction "K_2") (pintype "unspecified"))
      (node (ref "Z80") (pin "2") (pinfunction "K_2") (pintype "unspecified"))
      (node (ref "Z91") (pin "2") (pinfunction "K_2") (pintype "unspecified"))
    )
    (net (code "4") (name "P4") (class "Default")
      (node (ref "Z103") (pin "2") (pinfunction "K_2") (pintype "unspecified"))
      (node (ref "Z114") (pin "2") (pinfunction "K_2") (pintype "unspecified"))
      (node (ref "Z125") (pin "2") (pinfunction "K_2") (pintype "unspecified"))
      (node (ref "Z14") (pin "2") (pinfunction "K_2") (pintype "unspecified"))
      (node (ref "Z25") (pin "2") (pinfunction "K_2") (pintype "unspecified"))
      (node (ref "Z3") (pin "2") (pinfunction "K_2") (pintype "unspecified"))
      (node (ref "Z34") (pin "1") (pinfunction "A_1") (pintype "unspecified"))
      (node (ref "Z35") (pin "1") (pinfunction "A_1") (pintype "unspecified"))
      (node (ref "Z36") (pin "1") (pinfunction "A_1") (pintype "unspecified"))
      (node (ref "Z37") (pin "1") (pinfunction "A_1") (pintype "unspecified"))
      (node (ref "Z38") (pin "1") (pinfunction "A_1") (pintype "unspecified"))
      (node (ref "Z39") (pin "1") (pinfunction "A_1") (pintype "unspecified"))
      (node (ref "Z40") (pin "1") (pinfunction "A_1") (pintype "unspecified"))
      (node (ref "Z41") (pin "1") (pinfunction "A_1") (pintype "unspecified"))
      (node (ref "Z42") (pin "1") (pinfunction "A_1") (pintype "unspecified"))
      (node (ref "Z43") (pin "1") (pinfunction "A_1") (pintype "unspecified"))
      (node (ref "Z44") (pin "1") (pinfunction "A_1") (pintype "unspecified"))
      (node (ref "Z48") (pin "2") (pinfunction "K_2") (pintype "unspecified"))
      (node (ref "Z59") (pin "2") (pinfunction "K_2") (pintype "unspecified"))
      (node (ref "Z70") (pin "2") (pinfunction "K_2") (pintype "unspecified"))
      (node (ref "Z81") (pin "2") (pinfunction "K_2") (pintype "unspecified"))
      (node (ref "Z92") (pin "2") (pinfunction "K_2") (pintype "unspecified"))
    )
    (net (code "5") (name "P5") (class "Default")
      (node (ref "Z104") (pin "2") (pinfunction "K_2") (pintype "unspecified"))
      (node (ref "Z115") (pin "2") (pinfunction "K_2") (pintype "unspecified"))
      (node (ref "Z126") (pin "2") (pinfunction "K_2") (pintype "unspecified"))
      (node (ref "Z15") (pin "2") (pinfunction "K_2") (pintype "unspecified"))
      (node (ref "Z26") (pin "2") (pinfunction "K_2") (pintype "unspecified"))
      (node (ref "Z37") (pin "2") (pinfunction "K_2") (pintype "unspecified"))
      (node (ref "Z4") (pin "2") (pinfunction "K_2") (pintype "unspecified"))
      (node (ref "Z45") (pin "1") (pinfunction "A_1") (pintype "unspecified"))
      (node (ref "Z46") (pin "1") (pinfunction "A_1") (pintype "unspecified"))
      (node (ref "Z47") (pin "1") (pinfunction "A_1") (pintype "unspecified"))
      (node (ref "Z48") (pin "1") (pinfunction "A_1") (pintype "unspecified"))
      (node (ref "Z49") (pin "1") (pinfunction "A_1") (pintype "unspecified"))
      (node (ref "Z50") (pin "1") (pinfunction "A_1") (pintype "unspecified"))
      (node (ref "Z51") (pin "1") (pinfunction "A_1") (pintype "unspecified"))
      (node (ref "Z52") (pin "1") (pinfunction "A_1") (pintype "unspecified"))
      (node (ref "Z53") (pin "1") (pinfunction "A_1") (pintype "unspecified"))
      (node (ref "Z54") (pin "1") (pinfunction "A_1") (pintype "unspecified"))
      (node (ref "Z55") (pin "1") (pinfunction "A_1") (pintype "unspecified"))
      (node (ref "Z60") (pin "2") (pinfunction "K_2") (pintype "unspecified"))
      (node (ref "Z71") (pin "2") (pinfunction "K_2") (pintype "unspecified"))
      (node (ref "Z82") (pin "2") (pinfunction "K_2") (pintype "unspecified"))
      (node (ref "Z93") (pin "2") (pinfunction "K_2") (pintype "unspecified"))
    )
    (net (code "6") (name "P6") (class "Default")
      (node (ref "Z105") (pin "2") (pinfunction "K_2") (pintype "unspecified"))
      (node (ref "Z116") (pin "2") (pinfunction "K_2") (pintype "unspecified"))
      (node (ref "Z127") (pin "2") (pinfunction "K_2") (pintype "unspecified"))
      (node (ref "Z16") (pin "2") (pinfunction "K_2") (pintype "unspecified"))
      (node (ref "Z27") (pin "2") (pinfunction "K_2") (pintype "unspecified"))
      (node (ref "Z38") (pin "2") (pinfunction "K_2") (pintype "unspecified"))
      (node (ref "Z49") (pin "2") (pinfunction "K_2") (pintype "unspecified"))
      (node (ref "Z5") (pin "2") (pinfunction "K_2") (pintype "unspecified"))
      (node (ref "Z56") (pin "1") (pinfunction "A_1") (pintype "unspecified"))
      (node (ref "Z57") (pin "1") (pinfunction "A_1") (pintype "unspecified"))
      (node (ref "Z58") (pin "1") (pinfunction "A_1") (pintype "unspecified"))
      (node (ref "Z59") (pin "1") (pinfunction "A_1") (pintype "unspecified"))
      (node (ref "Z60") (pin "1") (pinfunction "A_1") (pintype "unspecified"))
      (node (ref "Z61") (pin "1") (pinfunction "A_1") (pintype "unspecified"))
      (node (ref "Z62") (pin "1") (pinfunction "A_1") (pintype "unspecified"))
      (node (ref "Z63") (pin "1") (pinfunction "A_1") (pintype "unspecified"))
      (node (ref "Z64") (pin "1") (pinfunction "A_1") (pintype "unspecified"))
      (node (ref "Z65") (pin "1") (pinfunction "A_1") (pintype "unspecified"))
      (node (ref "Z66") (pin "1") (pinfunction "A_1") (pintype "unspecified"))
      (node (ref "Z72") (pin "2") (pinfunction "K_2") (pintype "unspecified"))
      (node (ref "Z83") (pin "2") (pinfunction "K_2") (pintype "unspecified"))
      (node (ref "Z94") (pin "2") (pinfunction "K_2") (pintype "unspecified"))
    )
    (net (code "7") (name "P7") (class "Default")
      (node (ref "Z106") (pin "2") (pinfunction "K_2") (pintype "unspecified"))
      (node (ref "Z117") (pin "2") (pinfunction "K_2") (pintype "unspecified"))
      (node (ref "Z128") (pin "2") (pinfunction "K_2") (pintype "unspecified"))
      (node (ref "Z17") (pin "2") (pinfunction "K_2") (pintype "unspecified"))
      (node (ref "Z28") (pin "2") (pinfunction "K_2") (pintype "unspecified"))
      (node (ref "Z39") (pin "2") (pinfunction "K_2") (pintype "unspecified"))
      (node (ref "Z50") (pin "2") (pinfunction "K_2") (pintype "unspecified"))
      (node (ref "Z6") (pin "2") (pinfunction "K_2") (pintype "unspecified"))
      (node (ref "Z61") (pin "2") (pinfunction "K_2") (pintype "unspecified"))
      (node (ref "Z67") (pin "1") (pinfunction "A_1") (pintype "unspecified"))
      (node (ref "Z68") (pin "1") (pinfunction "A_1") (pintype "unspecified"))
      (node (ref "Z69") (pin "1") (pinfunction "A_1") (pintype "unspecified"))
      (node (ref "Z70") (pin "1") (pinfunction "A_1") (pintype "unspecified"))
      (node (ref "Z71") (pin "1") (pinfunction "A_1") (pintype "unspecified"))
      (node (ref "Z72") (pin "1") (pinfunction "A_1") (pintype "unspecified"))
      (node (ref "Z73") (pin "1") (pinfunction "A_1") (pintype "unspecified"))
      (node (ref "Z74") (pin "1") (pinfunction "A_1") (pintype "unspecified"))
      (node (ref "Z75") (pin "1") (pinfunction "A_1") (pintype "unspecified"))
      (node (ref "Z76") (pin "1") (pinfunction "A_1") (pintype "unspecified"))
      (node (ref "Z77") (pin "1") (pinfunction "A_1") (pintype "unspecified"))
      (node (ref "Z84") (pin "2") (pinfunction "K_2") (pintype "unspecified"))
      (node (ref "Z95") (pin "2") (pinfunction "K_2") (pintype "unspecified"))
    )
    (net (code "8") (name "P8") (class "Default")
      (node (ref "Z107") (pin "2") (pinfunction "K_2") (pintype "unspecified"))
      (node (ref "Z118") (pin "2") (pinfunction "K_2") (pintype "unspecified"))
      (node (ref "Z129") (pin "2") (pinfunction "K_2") (pintype "unspecified"))
      (node (ref "Z18") (pin "2") (pinfunction "K_2") (pintype "unspecified"))
      (node (ref "Z29") (pin "2") (pinfunction "K_2") (pintype "unspecified"))
      (node (ref "Z40") (pin "2") (pinfunction "K_2") (pintype "unspecified"))
      (node (ref "Z51") (pin "2") (pinfunction "K_2") (pintype "unspecified"))
      (node (ref "Z62") (pin "2") (pinfunction "K_2") (pintype "unspecified"))
      (node (ref "Z7") (pin "2") (pinfunction "K_2") (pintype "unspecified"))
      (node (ref "Z73") (pin "2") (pinfunction "K_2") (pintype "unspecified"))
      (node (ref "Z78") (pin "1") (pinfunction "A_1") (pintype "unspecified"))
      (node (ref "Z79") (pin "1") (pinfunction "A_1") (pintype "unspecified"))
      (node (ref "Z80") (pin "1") (pinfunction "A_1") (pintype "unspecified"))
      (node (ref "Z81") (pin "1") (pinfunction "A_1") (pintype "unspecified"))
      (node (ref "Z82") (pin "1") (pinfunction "A_1") (pintype "unspecified"))
      (node (ref "Z83") (pin "1") (pinfunction "A_1") (pintype "unspecified"))
      (node (ref "Z84") (pin "1") (pinfunction "A_1") (pintype "unspecified"))
      (node (ref "Z85") (pin "1") (pinfunction "A_1") (pintype "unspecified"))
      (node (ref "Z86") (pin "1") (pinfunction "A_1") (pintype "unspecified"))
      (node (ref "Z87") (pin "1") (pinfunction "A_1") (pintype "unspecified"))
      (node (ref "Z88") (pin "1") (pinfunction "A_1") (pintype "unspecified"))
      (node (ref "Z96") (pin "2") (pinfunction "K_2") (pintype "unspecified"))
    )
    (net (code "9") (name "P9") (class "Default")
      (node (ref "Z108") (pin "2") (pinfunction "K_2") (pintype "unspecified"))
      (node (ref "Z119") (pin "2") (pinfunction "K_2") (pintype "unspecified"))
      (node (ref "Z130") (pin "2") (pinfunction "K_2") (pintype "unspecified"))
      (node (ref "Z19") (pin "2") (pinfunction "K_2") (pintype "unspecified"))
      (node (ref "Z30") (pin "2") (pinfunction "K_2") (pintype "unspecified"))
      (node (ref "Z41") (pin "2") (pinfunction "K_2") (pintype "unspecified"))
      (node (ref "Z52") (pin "2") (pinfunction "K_2") (pintype "unspecified"))
      (node (ref "Z63") (pin "2") (pinfunction "K_2") (pintype "unspecified"))
      (node (ref "Z74") (pin "2") (pinfunction "K_2") (pintype "unspecified"))
      (node (ref "Z8") (pin "2") (pinfunction "K_2") (pintype "unspecified"))
      (node (ref "Z85") (pin "2") (pinfunction "K_2") (pintype "unspecified"))
      (node (ref "Z89") (pin "1") (pinfunction "A_1") (pintype "unspecified"))
      (node (ref "Z90") (pin "1") (pinfunction "A_1") (pintype "unspecified"))
      (node (ref "Z91") (pin "1") (pinfunction "A_1") (pintype "unspecified"))
      (node (ref "Z92") (pin "1") (pinfunction "A_1") (pintype "unspecified"))
      (node (ref "Z93") (pin "1") (pinfunction "A_1") (pintype "unspecified"))
      (node (ref "Z94") (pin "1") (pinfunction "A_1") (pintype "unspecified"))
      (node (ref "Z95") (pin "1") (pinfunction "A_1") (pintype "unspecified"))
      (node (ref "Z96") (pin "1") (pinfunction "A_1") (pintype "unspecified"))
      (node (ref "Z97") (pin "1") (pinfunction "A_1") (pintype "unspecified"))
      (node (ref "Z98") (pin "1") (pinfunction "A_1") (pintype "unspecified"))
      (node (ref "Z99") (pin "1") (pinfunction "A_1") (pintype "unspecified"))
    )
    (net (code "10") (name "P10") (class "Default")
      (node (ref "Z100") (pin "1") (pinfunction "A_1") (pintype "unspecified"))
      (node (ref "Z101") (pin "1") (pinfunction "A_1") (pintype "unspecified"))
      (node (ref "Z102") (pin "1") (pinfunction "A_1") (pintype "unspecified"))
      (node (ref "Z103") (pin "1") (pinfunction "A_1") (pintype "unspecified"))
      (node (ref "Z104") (pin "1") (pinfunction "A_1") (pintype "unspecified"))
      (node (ref "Z105") (pin "1") (pinfunction "A_1") (pintype "unspecified"))
      (node (ref "Z106") (pin "1") (pinfunction "A_1") (pintype "unspecified"))
      (node (ref "Z107") (pin "1") (pinfunction "A_1") (pintype "unspecified"))
      (node (ref "Z108") (pin "1") (pinfunction "A_1") (pintype "unspecified"))
      (node (ref "Z109") (pin "1") (pinfunction "A_1") (pintype "unspecified"))
      (node (ref "Z110") (pin "1") (pinfunction "A_1") (pintype "unspecified"))
      (node (ref "Z120") (pin "2") (pinfunction "K_2") (pintype "unspecified"))
      (node (ref "Z131") (pin "2") (pinfunction "K_2") (pintype "unspecified"))
      (node (ref "Z20") (pin "2") (pinfunction "K_2") (pintype "unspecified"))
      (node (ref "Z31") (pin "2") (pinfunction "K_2") (pintype "unspecified"))
      (node (ref "Z42") (pin "2") (pinfunction "K_2") (pintype "unspecified"))
      (node (ref "Z53") (pin "2") (pinfunction "K_2") (pintype "unspecified"))
      (node (ref "Z64") (pin "2") (pinfunction "K_2") (pintype "unspecified"))
      (node (ref "Z75") (pin "2") (pinfunction "K_2") (pintype "unspecified"))
      (node (ref "Z86") (pin "2") (pinfunction "K_2") (pintype "unspecified"))
      (node (ref "Z9") (pin "2") (pinfunction "K_2") (pintype "unspecified"))
      (node (ref "Z97") (pin "2") (pinfunction "K_2") (pintype "unspecified"))
    )
    (net (code "11") (name "P11") (class "Default")
      (node (ref "Z10") (pin "2") (pinfunction "K_2") (pintype "unspecified"))
      (node (ref "Z109") (pin "2") (pinfunction "K_2") (pintype "unspecified"))
      (node (ref "Z111") (pin "1") (pinfunction "A_1") (pintype "unspecified"))
      (node (ref "Z112") (pin "1") (pinfunction "A_1") (pintype "unspecified"))
      (node (ref "Z113") (pin "1") (pinfunction "A_1") (pintype "unspecified"))
      (node (ref "Z114") (pin "1") (pinfunction "A_1") (pintype "unspecified"))
      (node (ref "Z115") (pin "1") (pinfunction "A_1") (pintype "unspecified"))
      (node (ref "Z116") (pin "1") (pinfunction "A_1") (pintype "unspecified"))
      (node (ref "Z117") (pin "1") (pinfunction "A_1") (pintype "unspecified"))
      (node (ref "Z118") (pin "1") (pinfunction "A_1") (pintype "unspecified"))
      (node (ref "Z119") (pin "1") (pinfunction "A_1") (pintype "unspecified"))
      (node (ref "Z120") (pin "1") (pinfunction "A_1") (pintype "unspecified"))
      (node (ref "Z121") (pin "1") (pinfunction "A_1") (pintype "unspecified"))
      (node (ref "Z132") (pin "2") (pinfunction "K_2") (pintype "unspecified"))
      (node (ref "Z21") (pin "2") (pinfunction "K_2") (pintype "unspecified"))
      (node (ref "Z32") (pin "2") (pinfunction "K_2") (pintype "unspecified"))
      (node (ref "Z43") (pin "2") (pinfunction "K_2") (pintype "unspecified"))
      (node (ref "Z54") (pin "2") (pinfunction "K_2") (pintype "unspecified"))
      (node (ref "Z65") (pin "2") (pinfunction "K_2") (pintype "unspecified"))
      (node (ref "Z76") (pin "2") (pinfunction "K_2") (pintype "unspecified"))
      (node (ref "Z87") (pin "2") (pinfunction "K_2") (pintype "unspecified"))
      (node (ref "Z98") (pin "2") (pinfunction "K_2") (pintype "unspecified"))
    )
    (net (code "12") (name "P12") (class "Default")
      (node (ref "Z11") (pin "2") (pinfunction "K_2") (pintype "unspecified"))
      (node (ref "Z110") (pin "2") (pinfunction "K_2") (pintype "unspecified"))
      (node (ref "Z121") (pin "2") (pinfunction "K_2") (pintype "unspecified"))
      (node (ref "Z122") (pin "1") (pinfunction "A_1") (pintype "unspecified"))
      (node (ref "Z123") (pin "1") (pinfunction "A_1") (pintype "unspecified"))
      (node (ref "Z124") (pin "1") (pinfunction "A_1") (pintype "unspecified"))
      (node (ref "Z125") (pin "1") (pinfunction "A_1") (pintype "unspecified"))
      (node (ref "Z126") (pin "1") (pinfunction "A_1") (pintype "unspecified"))
      (node (ref "Z127") (pin "1") (pinfunction "A_1") (pintype "unspecified"))
      (node (ref "Z128") (pin "1") (pinfunction "A_1") (pintype "unspecified"))
      (node (ref "Z129") (pin "1") (pinfunction "A_1") (pintype "unspecified"))
      (node (ref "Z130") (pin "1") (pinfunction "A_1") (pintype "unspecified"))
      (node (ref "Z131") (pin "1") (pinfunction "A_1") (pintype "unspecified"))
      (node (ref "Z132") (pin "1") (pinfunction "A_1") (pintype "unspecified"))
      (node (ref "Z22") (pin "2") (pinfunction "K_2") (pintype "unspecified"))
      (node (ref "Z33") (pin "2") (pinfunction "K_2") (pintype "unspecified"))
      (node (ref "Z44") (pin "2") (pinfunction "K_2") (pintype "unspecified"))
      (node (ref "Z55") (pin "2") (pinfunction "K_2") (pintype "unspecified"))
      (node (ref "Z66") (pin "2") (pinfunction "K_2") (pintype "unspecified"))
      (node (ref "Z77") (pin "2") (pinfunction "K_2") (pintype "unspecified"))
      (node (ref "Z88") (pin "2") (pinfunction "K_2") (pintype "unspecified"))
      (node (ref "Z99") (pin "2") (pinfunction "K_2") (pintype "unspecified"))
    )
  )
)
